# STLINK.net
KiCad netlist of a schematic drawn in Altium Designer
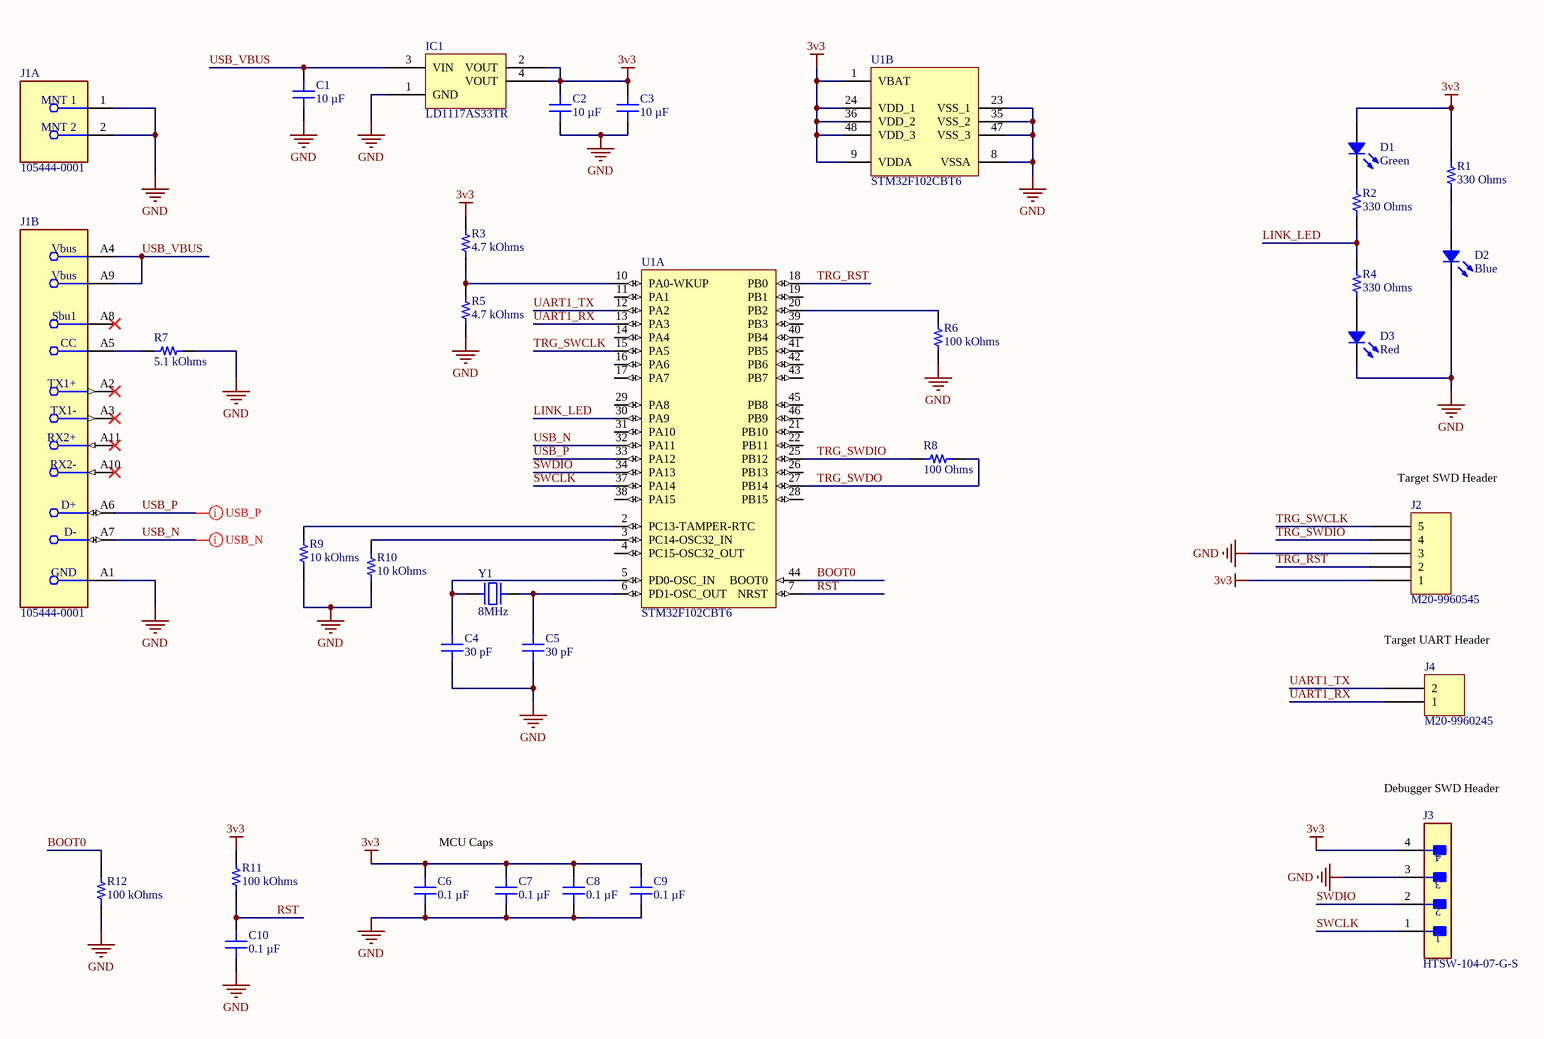
[diagram p0: STLINK.SchDoc]

(export (version "E")
  (design (tool "Eeschema 10.0.6"))
  (components
    (comp (ref "C1")
      (value "10 µF")
      (footprint "MURATA GRM188 0603_1608")
      (description "CAP CER 10UF 6.3V X5R 0603")
      (fields
        (field (name "PART NUMBER") "GRM188R60J106ME47D")
        (field (name "MANUFACTURER") "Murata Electronics")
      )
      (libsource (lib "Celestial Altium Library - altium_library") (part "Capacitor"))
    )
    (comp (ref "C2")
      (value "10 µF")
      (footprint "MURATA GRM188 0603_1608")
      (description "CAP CER 10UF 6.3V X5R 0603")
      (fields
        (field (name "PART NUMBER") "GRM188R60J106ME47D")
        (field (name "MANUFACTURER") "Murata Electronics")
      )
      (libsource (lib "Celestial Altium Library - altium_library") (part "Capacitor"))
    )
    (comp (ref "C3")
      (value "10 µF")
      (footprint "MURATA GRM188 0603_1608")
      (description "CAP CER 10UF 6.3V X5R 0603")
      (fields
        (field (name "PART NUMBER") "GRM188R60J106ME47D")
        (field (name "MANUFACTURER") "Murata Electronics")
      )
      (libsource (lib "Celestial Altium Library - altium_library") (part "Capacitor"))
    )
    (comp (ref "C4")
      (value "30 pF")
      (footprint "CAP 0603_1608")
      (description "CAP CER 30PF 50V C0G/NP0 0603")
      (fields
        (field (name "PART NUMBER") "0603N300J500CT")
        (field (name "MANUFACTURER") "Walsin Technology Corporation")
      )
      (libsource (lib "Celestial Altium Library - altium_library") (part "Capacitor"))
    )
    (comp (ref "C5")
      (value "30 pF")
      (footprint "CAP 0603_1608")
      (description "CAP CER 30PF 50V C0G/NP0 0603")
      (fields
        (field (name "PART NUMBER") "0603N300J500CT")
        (field (name "MANUFACTURER") "Walsin Technology Corporation")
      )
      (libsource (lib "Celestial Altium Library - altium_library") (part "Capacitor"))
    )
    (comp (ref "C6")
      (value "0.1 µF")
      (footprint "CAP 0603_1608")
      (description "CAP0603 X7R .1UF 10% 25V")
      (fields
        (field (name "PART NUMBER") "GMC10X7R104K25NT")
        (field (name "MANUFACTURER") "Cal-Chip Electronics, Inc.")
      )
      (libsource (lib "Celestial Altium Library - altium_library") (part "Capacitor"))
    )
    (comp (ref "C7")
      (value "0.1 µF")
      (footprint "CAP 0603_1608")
      (description "CAP0603 X7R .1UF 10% 25V")
      (fields
        (field (name "PART NUMBER") "GMC10X7R104K25NT")
        (field (name "MANUFACTURER") "Cal-Chip Electronics, Inc.")
      )
      (libsource (lib "Celestial Altium Library - altium_library") (part "Capacitor"))
    )
    (comp (ref "C8")
      (value "0.1 µF")
      (footprint "CAP 0603_1608")
      (description "CAP0603 X7R .1UF 10% 25V")
      (fields
        (field (name "PART NUMBER") "GMC10X7R104K25NT")
        (field (name "MANUFACTURER") "Cal-Chip Electronics, Inc.")
      )
      (libsource (lib "Celestial Altium Library - altium_library") (part "Capacitor"))
    )
    (comp (ref "C9")
      (value "0.1 µF")
      (footprint "CAP 0603_1608")
      (description "CAP0603 X7R .1UF 10% 25V")
      (fields
        (field (name "PART NUMBER") "GMC10X7R104K25NT")
        (field (name "MANUFACTURER") "Cal-Chip Electronics, Inc.")
      )
      (libsource (lib "Celestial Altium Library - altium_library") (part "Capacitor"))
    )
    (comp (ref "C10")
      (value "0.1 µF")
      (footprint "CAP 0603_1608")
      (description "CAP0603 X7R .1UF 10% 25V")
      (fields
        (field (name "PART NUMBER") "GMC10X7R104K25NT")
        (field (name "MANUFACTURER") "Cal-Chip Electronics, Inc.")
      )
      (libsource (lib "Celestial Altium Library - altium_library") (part "Capacitor"))
    )
    (comp (ref "D1")
      (value "Green")
      (footprint "LED 0603_1608 GREEN")
      (description "LED GREEN CLEAR 2SMD")
      (fields
        (field (name "PART NUMBER") "19-213/GVC-AMNB/3T")
        (field (name "MANUFACTURER") "Everlight Electronics Co Ltd")
      )
      (libsource (lib "Celestial Altium Library - altium_library") (part "LED"))
    )
    (comp (ref "D2")
      (value "Blue")
      (footprint "LED 0603_1608 BLUE")
      (description "LED BLUE CLEAR 2SMD")
      (fields
        (field (name "PART NUMBER") "19-217/B7C-ZL2N1B3X/3T")
        (field (name "MANUFACTURER") "Everlight Electronics Co Ltd")
      )
      (libsource (lib "Celestial Altium Library - altium_library") (part "LED"))
    )
    (comp (ref "D3")
      (value "Red")
      (footprint "LED 0603_1608 RED")
      (description "LED RED CLEAR 2SMD")
      (fields
        (field (name "PART NUMBER") "19-213SDRC/S259/TR8")
        (field (name "MANUFACTURER") "Everlight Electronics Co Ltd")
      )
      (libsource (lib "Celestial Altium Library - altium_library") (part "LED"))
    )
    (comp (ref "IC1")
      (value "LD1117AS33TR")
      (footprint "ST SOT-223")
      (description "IC REG LINEAR 3.3V 1A SOT223")
      (fields (field (name "MANUFACTURER") "STMicroelectronics"))
      (libsource (lib "Celestial Altium Library - altium_library") (part "ST LD1117"))
    )
    (comp (ref "J1")
      (value "105444-0001")
      (footprint "FP-105444-0001-MFG")
      (description "CONN PLUG USB3.1 TYPEC BRD EDGE")
      (libsource (lib "Altium Content Vault") (part "182575ff53d3110fee9f5872a599f53"))
    )
    (comp (ref "J2")
      (value "M20-9960545")
      (footprint "HARWIN M20-9960545")
      (description "CONN HEADER R/A 5POS 2.54MM")
      (fields (field (name "MANUFACTURER") "Harwin Inc."))
      (libsource (lib "Celestial Altium Library - altium_library") (part "5 Pin"))
    )
    (comp (ref "J3")
      (value "HTSW-104-07-G-S")
      (footprint "FP-HTSW-104-07-G-S-MFG")
      (description "CONN HEADER VERT 4POS 2.54MM")
      (libsource (lib "Altium Content Vault") (part "299a8cea1bdcbc3624fe62c390fa72c"))
    )
    (comp (ref "J4")
      (value "M20-9960245")
      (footprint "HARWIN M20-9960245")
      (description "CONN HEADER R/A 2POS 2.54MM")
      (fields (field (name "MANUFACTURER") "Harwin Inc."))
      (libsource (lib "Celestial Altium Library - altium_library") (part "2 Pin"))
    )
    (comp (ref "R1")
      (value "330 Ohms")
      (footprint "KOA RES RK73 RN73 0603_1608")
      (description "RES 330 OHM 0.5% 1/5W 0603")
      (fields
        (field (name "PART NUMBER") "RS73F1JTTD3300D")
        (field (name "MANUFACTURER") "KOA Speer Electronics, Inc.")
      )
      (libsource (lib "Celestial Altium Library - altium_library") (part "Resistor"))
    )
    (comp (ref "R2")
      (value "330 Ohms")
      (footprint "KOA RES RK73 RN73 0603_1608")
      (description "RES 330 OHM 0.5% 1/5W 0603")
      (fields
        (field (name "PART NUMBER") "RS73F1JTTD3300D")
        (field (name "MANUFACTURER") "KOA Speer Electronics, Inc.")
      )
      (libsource (lib "Celestial Altium Library - altium_library") (part "Resistor"))
    )
    (comp (ref "R3")
      (value "4.7 kOhms")
      (footprint "RES 0603_1608")
      (description "RES 4.7K OHM 0.05% 1/8W 0603")
      (fields
        (field (name "PART NUMBER") "ERA-3VRW4701V")
        (field (name "MANUFACTURER") "Panasonic Electronic Components")
      )
      (libsource (lib "Celestial Altium Library - altium_library") (part "Resistor"))
    )
    (comp (ref "R4")
      (value "330 Ohms")
      (footprint "KOA RES RK73 RN73 0603_1608")
      (description "RES 330 OHM 0.5% 1/5W 0603")
      (fields
        (field (name "PART NUMBER") "RS73F1JTTD3300D")
        (field (name "MANUFACTURER") "KOA Speer Electronics, Inc.")
      )
      (libsource (lib "Celestial Altium Library - altium_library") (part "Resistor"))
    )
    (comp (ref "R5")
      (value "4.7 kOhms")
      (footprint "RES 0603_1608")
      (description "RES 4.7K OHM 0.05% 1/8W 0603")
      (fields
        (field (name "PART NUMBER") "ERA-3VRW4701V")
        (field (name "MANUFACTURER") "Panasonic Electronic Components")
      )
      (libsource (lib "Celestial Altium Library - altium_library") (part "Resistor"))
    )
    (comp (ref "R6")
      (value "100 kOhms")
      (footprint "RES 0603_1608")
      (description "MCT 0603-05 0.1% AT P5 100K")
      (fields
        (field (name "PART NUMBER") "MCT0603MG1003BP500")
        (field (name "MANUFACTURER") "Vishay Beyschlag/Draloric/BC Components")
      )
      (libsource (lib "Celestial Altium Library - altium_library") (part "Resistor"))
    )
    (comp (ref "R7")
      (value "5.1 kOhms")
      (footprint "RES 0603_1608")
      (description "RES 5.1K OHM 0.1% 1/10W 0603")
      (fields (field (name "PART NUMBER") "TNPW06035K10BYEN") (field (name "MANUFACTURER") "Vishay Dale"))
      (libsource (lib "Celestial Altium Library - altium_library") (part "Resistor"))
    )
    (comp (ref "R8")
      (value "100 Ohms")
      (footprint "KOA RES RK73 RN73 0603_1608")
      (description "RES 100 OHM 0.1% 1/5W 0603")
      (fields
        (field (name "PART NUMBER") "RS73G1JTTD1000B")
        (field (name "MANUFACTURER") "KOA Speer Electronics, Inc.")
      )
      (libsource (lib "Celestial Altium Library - altium_library") (part "Resistor"))
    )
    (comp (ref "R9")
      (value "10 kOhms")
      (footprint "RES 0603_1608")
      (description "MCT 0603-05 0.1% AT P5 10K")
      (fields
        (field (name "PART NUMBER") "MCT0603MG1002BP500")
        (field (name "MANUFACTURER") "Vishay Beyschlag/Draloric/BC Components")
      )
      (libsource (lib "Celestial Altium Library - altium_library") (part "Resistor"))
    )
    (comp (ref "R10")
      (value "10 kOhms")
      (footprint "RES 0603_1608")
      (description "MCT 0603-05 0.1% AT P5 10K")
      (fields
        (field (name "PART NUMBER") "MCT0603MG1002BP500")
        (field (name "MANUFACTURER") "Vishay Beyschlag/Draloric/BC Components")
      )
      (libsource (lib "Celestial Altium Library - altium_library") (part "Resistor"))
    )
    (comp (ref "R11")
      (value "100 kOhms")
      (footprint "RES 0603_1608")
      (description "MCT 0603-05 0.1% AT P5 100K")
      (fields
        (field (name "PART NUMBER") "MCT0603MG1003BP500")
        (field (name "MANUFACTURER") "Vishay Beyschlag/Draloric/BC Components")
      )
      (libsource (lib "Celestial Altium Library - altium_library") (part "Resistor"))
    )
    (comp (ref "R12")
      (value "100 kOhms")
      (footprint "RES 0603_1608")
      (description "MCT 0603-05 0.1% AT P5 100K")
      (fields
        (field (name "PART NUMBER") "MCT0603MG1003BP500")
        (field (name "MANUFACTURER") "Vishay Beyschlag/Draloric/BC Components")
      )
      (libsource (lib "Celestial Altium Library - altium_library") (part "Resistor"))
    )
    (comp (ref "U1")
      (value "STM32F102CBT6")
      (footprint "STM-LQFP48_N")
      (libsource (lib "Altium Content Vault") (part "MC-ARM-STM32F102X8_B-SQ48"))
    )
    (comp (ref "Y1")
      (value "8MHz")
      (footprint "TXC 9C")
      (description "CRYSTAL 8.0000MHZ 20PF SMD")
      (fields (field (name "PART NUMBER") "9C-8.000MBBK-T") (field (name "MANUFACTURER") "TXC CORPORATION"))
      (libsource (lib "Celestial Altium Library - altium_library") (part "TXC Crystal 9C"))
    )
  )
  (nets
    (net (code "1") (name "/BOOT0") (class "Default")
      (node (ref "R12") (pin "2") (pinfunction "2_2") (pintype "passive"))
      (node (ref "U1") (pin "44") (pinfunction "BOOT0_44") (pintype "input"))
    )
    (net (code "2") (name "/LINK_LED") (class "Default")
      (node (ref "R2") (pin "1") (pinfunction "1_1") (pintype "passive"))
      (node (ref "R4") (pin "1") (pinfunction "1_1") (pintype "passive"))
      (node (ref "U1") (pin "30") (pinfunction "PA9_30") (pintype "bidirectional"))
    )
    (net (code "3") (name "/RST") (class "Default")
      (node (ref "C10") (pin "2") (pinfunction "2_2") (pintype "passive"))
      (node (ref "R11") (pin "1") (pinfunction "1_1") (pintype "passive"))
      (node (ref "U1") (pin "7") (pinfunction "NRST_7") (pintype "bidirectional"))
    )
    (net (code "4") (name "/SWCLK") (class "Default")
      (node (ref "J3") (pin "1") (pinfunction "1_1") (pintype "passive"))
      (node (ref "U1") (pin "37") (pinfunction "PA14_37") (pintype "bidirectional"))
    )
    (net (code "5") (name "/SWDIO") (class "Default")
      (node (ref "J3") (pin "2") (pinfunction "2_2") (pintype "passive"))
      (node (ref "U1") (pin "34") (pinfunction "PA13_34") (pintype "bidirectional"))
    )
    (net (code "6") (name "/TRG_RST") (class "Default")
      (node (ref "J2") (pin "2") (pinfunction "2_2") (pintype "passive"))
      (node (ref "U1") (pin "18") (pinfunction "PB0_18") (pintype "bidirectional"))
    )
    (net (code "7") (name "/TRG_SWCLK") (class "Default")
      (node (ref "J2") (pin "5") (pinfunction "5_5") (pintype "passive"))
      (node (ref "U1") (pin "15") (pinfunction "PA5_15") (pintype "bidirectional"))
    )
    (net (code "8") (name "/TRG_SWDIO") (class "Default")
      (node (ref "J2") (pin "4") (pinfunction "4_4") (pintype "passive"))
      (node (ref "R8") (pin "1") (pinfunction "1_1") (pintype "passive"))
      (node (ref "U1") (pin "25") (pinfunction "PB12_25") (pintype "bidirectional"))
    )
    (net (code "9") (name "/TRG_SWDO") (class "Default")
      (node (ref "R8") (pin "2") (pinfunction "2_2") (pintype "passive"))
      (node (ref "U1") (pin "27") (pinfunction "PB14_27") (pintype "bidirectional"))
    )
    (net (code "10") (name "/UART1_RX") (class "Default")
      (node (ref "J4") (pin "1") (pinfunction "1_1") (pintype "passive"))
      (node (ref "U1") (pin "13") (pinfunction "PA3_13") (pintype "bidirectional"))
    )
    (net (code "11") (name "/UART1_TX") (class "Default")
      (node (ref "J4") (pin "2") (pinfunction "2_2") (pintype "passive"))
      (node (ref "U1") (pin "12") (pinfunction "PA2_12") (pintype "bidirectional"))
    )
    (net (code "12") (name "/USB_N") (class "Default")
      (node (ref "J1") (pin "A7") (pinfunction "D-_A7") (pintype "bidirectional"))
      (node (ref "U1") (pin "32") (pinfunction "PA11_32") (pintype "bidirectional"))
    )
    (net (code "13") (name "/USB_P") (class "Default")
      (node (ref "J1") (pin "A6") (pinfunction "D+_A6") (pintype "bidirectional"))
      (node (ref "U1") (pin "33") (pinfunction "PA12_33") (pintype "bidirectional"))
    )
    (net (code "14") (name "/USB_VBUS") (class "Default")
      (node (ref "C1") (pin "1") (pinfunction "1_1") (pintype "passive"))
      (node (ref "IC1") (pin "3") (pinfunction "VIN_3") (pintype "passive"))
      (node (ref "J1") (pin "A4") (pinfunction "Vbus_A4") (pintype "power_in"))
      (node (ref "J1") (pin "A9") (pinfunction "Vbus_A9") (pintype "power_in"))
    )
    (net (code "15") (name "3v3") (class "Default")
      (node (ref "C2") (pin "2") (pinfunction "2_2") (pintype "passive"))
      (node (ref "C3") (pin "2") (pinfunction "2_2") (pintype "passive"))
      (node (ref "C6") (pin "2") (pinfunction "2_2") (pintype "passive"))
      (node (ref "C7") (pin "2") (pinfunction "2_2") (pintype "passive"))
      (node (ref "C8") (pin "2") (pinfunction "2_2") (pintype "passive"))
      (node (ref "C9") (pin "2") (pinfunction "2_2") (pintype "passive"))
      (node (ref "D1") (pin "1") (pinfunction "1_1") (pintype "passive"))
      (node (ref "IC1") (pin "2") (pinfunction "VOUT_2") (pintype "passive"))
      (node (ref "IC1") (pin "4") (pinfunction "VOUT_4") (pintype "passive"))
      (node (ref "J2") (pin "1") (pinfunction "1_1") (pintype "passive"))
      (node (ref "J3") (pin "4") (pinfunction "4_4") (pintype "passive"))
      (node (ref "R1") (pin "2") (pinfunction "2_2") (pintype "passive"))
      (node (ref "R11") (pin "2") (pinfunction "2_2") (pintype "passive"))
      (node (ref "R3") (pin "2") (pinfunction "2_2") (pintype "passive"))
      (node (ref "U1") (pin "1") (pinfunction "VBAT_1") (pintype "power_in"))
      (node (ref "U1") (pin "24") (pinfunction "VDD_1_24") (pintype "power_in"))
      (node (ref "U1") (pin "36") (pinfunction "VDD_2_36") (pintype "power_in"))
      (node (ref "U1") (pin "48") (pinfunction "VDD_3_48") (pintype "power_in"))
      (node (ref "U1") (pin "9") (pinfunction "VDDA_9") (pintype "power_in"))
    )
    (net (code "16") (name "GND") (class "Default")
      (node (ref "C1") (pin "2") (pinfunction "2_2") (pintype "passive"))
      (node (ref "C10") (pin "1") (pinfunction "1_1") (pintype "passive"))
      (node (ref "C2") (pin "1") (pinfunction "1_1") (pintype "passive"))
      (node (ref "C3") (pin "1") (pinfunction "1_1") (pintype "passive"))
      (node (ref "C4") (pin "1") (pinfunction "1_1") (pintype "passive"))
      (node (ref "C5") (pin "1") (pinfunction "1_1") (pintype "passive"))
      (node (ref "C6") (pin "1") (pinfunction "1_1") (pintype "passive"))
      (node (ref "C7") (pin "1") (pinfunction "1_1") (pintype "passive"))
      (node (ref "C8") (pin "1") (pinfunction "1_1") (pintype "passive"))
      (node (ref "C9") (pin "1") (pinfunction "1_1") (pintype "passive"))
      (node (ref "D2") (pin "2") (pinfunction "2_2") (pintype "passive"))
      (node (ref "D3") (pin "2") (pinfunction "2_2") (pintype "passive"))
      (node (ref "IC1") (pin "1") (pinfunction "GND_1") (pintype "passive"))
      (node (ref "J1") (pin "1") (pinfunction "MNT_1_1") (pintype "passive"))
      (node (ref "J1") (pin "2") (pinfunction "MNT_2_2") (pintype "passive"))
      (node (ref "J1") (pin "A1") (pinfunction "GND_A1") (pintype "power_in"))
      (node (ref "J2") (pin "3") (pinfunction "3_3") (pintype "passive"))
      (node (ref "J3") (pin "3") (pinfunction "3_3") (pintype "passive"))
      (node (ref "R10") (pin "1") (pinfunction "1_1") (pintype "passive"))
      (node (ref "R12") (pin "1") (pinfunction "1_1") (pintype "passive"))
      (node (ref "R5") (pin "1") (pinfunction "1_1") (pintype "passive"))
      (node (ref "R6") (pin "1") (pinfunction "1_1") (pintype "passive"))
      (node (ref "R7") (pin "2") (pinfunction "2_2") (pintype "passive"))
      (node (ref "R9") (pin "1") (pinfunction "1_1") (pintype "passive"))
      (node (ref "U1") (pin "23") (pinfunction "VSS_1_23") (pintype "power_in"))
      (node (ref "U1") (pin "35") (pinfunction "VSS_2_35") (pintype "power_in"))
      (node (ref "U1") (pin "47") (pinfunction "VSS_3_47") (pintype "power_in"))
      (node (ref "U1") (pin "8") (pinfunction "VSSA_8") (pintype "power_in"))
    )
    (net (code "17") (name "Net-(D1-Pad2)") (class "Default")
      (node (ref "D1") (pin "2") (pinfunction "2_2") (pintype "passive"))
      (node (ref "R2") (pin "2") (pinfunction "2_2") (pintype "passive"))
    )
    (net (code "18") (name "Net-(D2-Pad1)") (class "Default")
      (node (ref "D2") (pin "1") (pinfunction "1_1") (pintype "passive"))
      (node (ref "R1") (pin "1") (pinfunction "1_1") (pintype "passive"))
    )
    (net (code "19") (name "Net-(D3-Pad1)") (class "Default")
      (node (ref "D3") (pin "1") (pinfunction "1_1") (pintype "passive"))
      (node (ref "R4") (pin "2") (pinfunction "2_2") (pintype "passive"))
    )
    (net (code "20") (name "Net-(J1B-CC)") (class "Default")
      (node (ref "J1") (pin "A5") (pinfunction "CC_A5") (pintype "passive"))
      (node (ref "R7") (pin "1") (pinfunction "1_1") (pintype "passive"))
    )
    (net (code "21") (name "Net-(U1A-PA0-WKUP)") (class "Default")
      (node (ref "R3") (pin "1") (pinfunction "1_1") (pintype "passive"))
      (node (ref "R5") (pin "2") (pinfunction "2_2") (pintype "passive"))
      (node (ref "U1") (pin "10") (pinfunction "PA0-WKUP_10") (pintype "bidirectional"))
    )
    (net (code "22") (name "Net-(U1A-PB2)") (class "Default")
      (node (ref "R6") (pin "2") (pinfunction "2_2") (pintype "passive"))
      (node (ref "U1") (pin "20") (pinfunction "PB2_20") (pintype "bidirectional"))
    )
    (net (code "23") (name "Net-(U1A-PC13-TAMPER-RTC)") (class "Default")
      (node (ref "R9") (pin "2") (pinfunction "2_2") (pintype "passive"))
      (node (ref "U1") (pin "2") (pinfunction "PC13-TAMPER-RTC_2") (pintype "bidirectional"))
    )
    (net (code "24") (name "Net-(U1A-PC14-OSC32_IN)") (class "Default")
      (node (ref "R10") (pin "2") (pinfunction "2_2") (pintype "passive"))
      (node (ref "U1") (pin "3") (pinfunction "PC14-OSC32_IN_3") (pintype "bidirectional"))
    )
    (net (code "25") (name "Net-(U1A-PD0-OSC_IN)") (class "Default")
      (node (ref "C4") (pin "2") (pinfunction "2_2") (pintype "passive"))
      (node (ref "U1") (pin "5") (pinfunction "PD0-OSC_IN_5") (pintype "bidirectional"))
      (node (ref "Y1") (pin "1") (pinfunction "1_1") (pintype "passive"))
    )
    (net (code "26") (name "Net-(U1A-PD1-OSC_OUT)") (class "Default")
      (node (ref "C5") (pin "2") (pinfunction "2_2") (pintype "passive"))
      (node (ref "U1") (pin "6") (pinfunction "PD1-OSC_OUT_6") (pintype "bidirectional"))
      (node (ref "Y1") (pin "2") (pinfunction "2_2") (pintype "passive"))
    )
    (net (code "27") (name "unconnected-(J1B-RX2+-PadA11)") (class "Default")
      (node (ref "J1") (pin "A11") (pinfunction "RX2+_A11") (pintype "input+no_connect"))
    )
    (net (code "28") (name "unconnected-(J1B-RX2--PadA10)") (class "Default")
      (node (ref "J1") (pin "A10") (pinfunction "RX2-_A10") (pintype "input+no_connect"))
    )
    (net (code "29") (name "unconnected-(J1B-Sbu1-PadA8)") (class "Default")
      (node (ref "J1") (pin "A8") (pinfunction "Sbu1_A8") (pintype "passive+no_connect"))
    )
    (net (code "30") (name "unconnected-(J1B-TX1+-PadA2)") (class "Default")
      (node (ref "J1") (pin "A2") (pinfunction "TX1+_A2") (pintype "output+no_connect"))
    )
    (net (code "31") (name "unconnected-(J1B-TX1--PadA3)") (class "Default")
      (node (ref "J1") (pin "A3") (pinfunction "TX1-_A3") (pintype "output+no_connect"))
    )
    (net (code "32") (name "unconnected-(U1A-PA1-Pad11)") (class "Default")
      (node (ref "U1") (pin "11") (pinfunction "PA1_11") (pintype "bidirectional"))
    )
    (net (code "33") (name "unconnected-(U1A-PA4-Pad14)") (class "Default")
      (node (ref "U1") (pin "14") (pinfunction "PA4_14") (pintype "bidirectional"))
    )
    (net (code "34") (name "unconnected-(U1A-PA6-Pad16)") (class "Default")
      (node (ref "U1") (pin "16") (pinfunction "PA6_16") (pintype "bidirectional"))
    )
    (net (code "35") (name "unconnected-(U1A-PA7-Pad17)") (class "Default")
      (node (ref "U1") (pin "17") (pinfunction "PA7_17") (pintype "bidirectional"))
    )
    (net (code "36") (name "unconnected-(U1A-PA8-Pad29)") (class "Default")
      (node (ref "U1") (pin "29") (pinfunction "PA8_29") (pintype "bidirectional"))
    )
    (net (code "37") (name "unconnected-(U1A-PA10-Pad31)") (class "Default")
      (node (ref "U1") (pin "31") (pinfunction "PA10_31") (pintype "bidirectional"))
    )
    (net (code "38") (name "unconnected-(U1A-PA15-Pad38)") (class "Default")
      (node (ref "U1") (pin "38") (pinfunction "PA15_38") (pintype "bidirectional"))
    )
    (net (code "39") (name "unconnected-(U1A-PB1-Pad19)") (class "Default")
      (node (ref "U1") (pin "19") (pinfunction "PB1_19") (pintype "bidirectional"))
    )
    (net (code "40") (name "unconnected-(U1A-PB3-Pad39)") (class "Default")
      (node (ref "U1") (pin "39") (pinfunction "PB3_39") (pintype "bidirectional"))
    )
    (net (code "41") (name "unconnected-(U1A-PB4-Pad40)") (class "Default")
      (node (ref "U1") (pin "40") (pinfunction "PB4_40") (pintype "bidirectional"))
    )
    (net (code "42") (name "unconnected-(U1A-PB5-Pad41)") (class "Default")
      (node (ref "U1") (pin "41") (pinfunction "PB5_41") (pintype "bidirectional"))
    )
    (net (code "43") (name "unconnected-(U1A-PB6-Pad42)") (class "Default")
      (node (ref "U1") (pin "42") (pinfunction "PB6_42") (pintype "bidirectional"))
    )
    (net (code "44") (name "unconnected-(U1A-PB7-Pad43)") (class "Default")
      (node (ref "U1") (pin "43") (pinfunction "PB7_43") (pintype "bidirectional"))
    )
    (net (code "45") (name "unconnected-(U1A-PB8-Pad45)") (class "Default")
      (node (ref "U1") (pin "45") (pinfunction "PB8_45") (pintype "bidirectional"))
    )
    (net (code "46") (name "unconnected-(U1A-PB9-Pad46)") (class "Default")
      (node (ref "U1") (pin "46") (pinfunction "PB9_46") (pintype "bidirectional"))
    )
    (net (code "47") (name "unconnected-(U1A-PB10-Pad21)") (class "Default")
      (node (ref "U1") (pin "21") (pinfunction "PB10_21") (pintype "bidirectional"))
    )
    (net (code "48") (name "unconnected-(U1A-PB11-Pad22)") (class "Default")
      (node (ref "U1") (pin "22") (pinfunction "PB11_22") (pintype "bidirectional"))
    )
    (net (code "49") (name "unconnected-(U1A-PB13-Pad26)") (class "Default")
      (node (ref "U1") (pin "26") (pinfunction "PB13_26") (pintype "bidirectional"))
    )
    (net (code "50") (name "unconnected-(U1A-PB15-Pad28)") (class "Default")
      (node (ref "U1") (pin "28") (pinfunction "PB15_28") (pintype "bidirectional"))
    )
    (net (code "51") (name "unconnected-(U1A-PC15-OSC32_OUT-Pad4)") (class "Default")
      (node (ref "U1") (pin "4") (pinfunction "PC15-OSC32_OUT_4") (pintype "bidirectional"))
    )
  )
)
